# Radio2_Cm.net
KiCad netlist of a schematic drawn in EAGLE
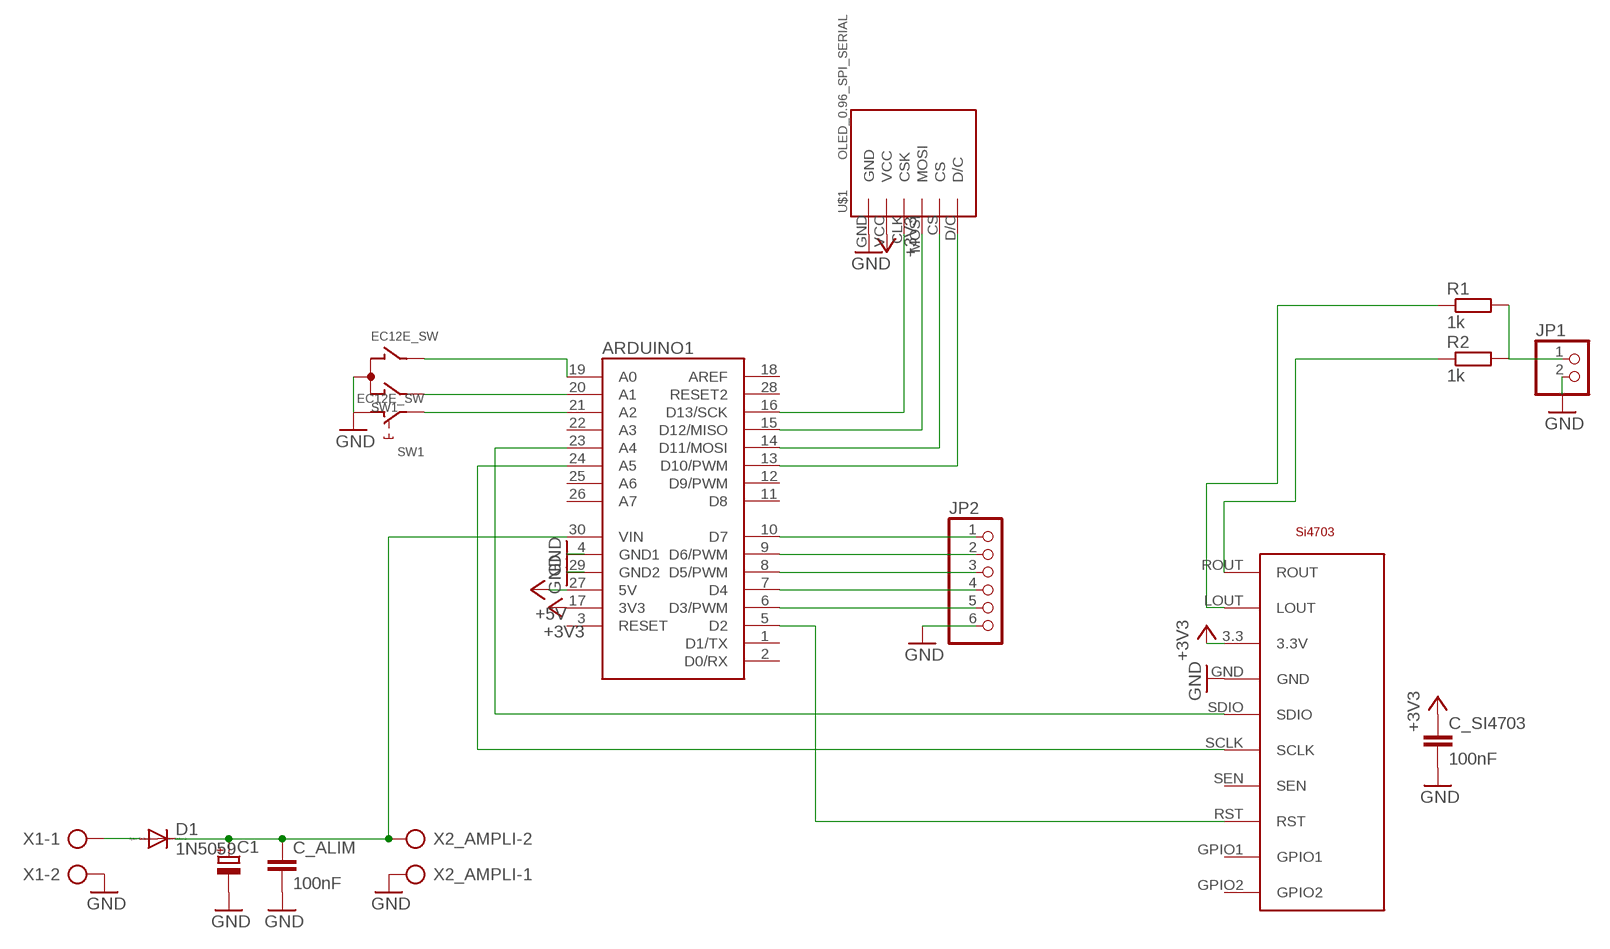
[diagram p0: schematic, sheet 1]

(export (version "E")
  (design (tool "Eeschema 10.0.6"))
  (components
    (comp (ref "ARDUINO1")
      (value "ARDUINO_NANO")
      (footprint "eagle-import:ARDUINO_NANO")
      (libsource (lib "eagle-import") (part "ARDUINO_NANO"))
    )
    (comp (ref "C1")
      (value "CPOL-EUE7.5-16")
      (footprint "eagle-import:E7,5-16")
      (libsource (lib "eagle-import") (part "CPOL-EUE7.5-16"))
    )
    (comp (ref "C_ALIM")
      (value "100nF")
      (footprint "eagle-import:C025-024X044")
      (libsource (lib "eagle-import") (part "C-EU025-024X044"))
    )
    (comp (ref "C_SI4703")
      (value "100nF")
      (footprint "eagle-import:C025-024X044")
      (libsource (lib "eagle-import") (part "C-EU025-024X044"))
    )
    (comp (ref "D1")
      (value "1N5059")
      (footprint "eagle-import:DO204-10")
      (libsource (lib "eagle-import") (part "1N5059"))
    )
    (comp (ref "JP1")
      (value "PINHD-1X2")
      (footprint "eagle-import:1X02")
      (libsource (lib "eagle-import") (part "PINHD-1X2"))
    )
    (comp (ref "JP2")
      (value "PINHD-1X6")
      (footprint "eagle-import:1X06")
      (libsource (lib "eagle-import") (part "PINHD-1X6"))
    )
    (comp (ref "R1")
      (value "1k")
      (footprint "eagle-import:0207_10")
      (libsource (lib "eagle-import") (part "R-EU_0207/10"))
    )
    (comp (ref "R2")
      (value "1k")
      (footprint "eagle-import:0207_10")
      (libsource (lib "eagle-import") (part "R-EU_0207/10"))
    )
    (comp (ref "SW1")
      (value "EC12E_SW")
      (footprint "eagle-import:ALPS_EC12E_SW")
      (fields (field (name "MPN") "EC12E2424407"))
      (libsource (lib "eagle-import") (part "EC12E_SW"))
    )
    (comp (ref "U$1")
      (value "OLED_0.96_SPI_SERIAL")
      (footprint "eagle-import:OLED_9.96_SPI_SERIAL")
      (libsource (lib "eagle-import") (part "OLED_0.96_SPI_SERIAL"))
    )
    (comp (ref "U$3")
      (value "SI4703")
      (footprint "eagle-import:SI4703")
      (libsource (lib "eagle-import") (part "SI4703"))
    )
    (comp (ref "X1")
      (value "AK300/2")
      (footprint "eagle-import:AK300_2")
      (libsource (lib "eagle-import") (part "AK300/2"))
    )
    (comp (ref "X2_AMPLI")
      (value "AK300/2")
      (footprint "eagle-import:AK300_2")
      (libsource (lib "eagle-import") (part "AK300/2"))
    )
  )
  (nets
    (net (code "1") (name "+3V3") (class "Default")
      (node (ref "ARDUINO1") (pin "17") (pinfunction "3V3_17") (pintype "power_in"))
      (node (ref "C_SI4703") (pin "1") (pinfunction "1_1") (pintype "passive"))
      (node (ref "U$1") (pin "VCC") (pinfunction "VCC_VCC") (pintype "bidirectional"))
      (node (ref "U$3") (pin "3.3") (pinfunction "3.3V_3.3") (pintype "bidirectional"))
    )
    (net (code "2") (name "+5V") (class "Default")
      (node (ref "ARDUINO1") (pin "27") (pinfunction "5V_27") (pintype "power_in"))
    )
    (net (code "3") (name "/RESET2") (class "Default")
      (node (ref "ARDUINO1") (pin "28") (pinfunction "RESET2_28") (pintype "power_in"))
    )
    (net (code "4") (name "GND") (class "Default")
      (node (ref "ARDUINO1") (pin "29") (pinfunction "GND2_29") (pintype "power_in"))
      (node (ref "ARDUINO1") (pin "4") (pinfunction "GND1_4") (pintype "power_in"))
      (node (ref "C1") (pin "-") (pinfunction "-_-") (pintype "passive"))
      (node (ref "C_ALIM") (pin "2") (pinfunction "2_2") (pintype "passive"))
      (node (ref "C_SI4703") (pin "2") (pinfunction "2_2") (pintype "passive"))
      (node (ref "JP1") (pin "2") (pinfunction "2_2") (pintype "passive"))
      (node (ref "JP2") (pin "6") (pinfunction "6_6") (pintype "passive"))
      (node (ref "SW1") (pin "C") (pinfunction "C_C") (pintype "passive"))
      (node (ref "SW1") (pin "D") (pinfunction "1_D") (pintype "passive"))
      (node (ref "U$1") (pin "GND") (pinfunction "GND_GND") (pintype "bidirectional"))
      (node (ref "U$3") (pin "GND") (pinfunction "GND_GND") (pintype "bidirectional"))
      (node (ref "X1") (pin "2") (pinfunction "KL_2") (pintype "passive"))
      (node (ref "X2_AMPLI") (pin "1") (pinfunction "KL_1") (pintype "passive"))
    )
    (net (code "5") (name "Net-(ARDUINO1-A0)") (class "Default")
      (node (ref "ARDUINO1") (pin "19") (pinfunction "A0_19") (pintype "bidirectional"))
      (node (ref "SW1") (pin "B") (pinfunction "B_B") (pintype "passive"))
    )
    (net (code "6") (name "Net-(ARDUINO1-A1)") (class "Default")
      (node (ref "ARDUINO1") (pin "20") (pinfunction "A1_20") (pintype "bidirectional"))
      (node (ref "SW1") (pin "A") (pinfunction "A_A") (pintype "passive"))
    )
    (net (code "7") (name "Net-(ARDUINO1-A2)") (class "Default")
      (node (ref "ARDUINO1") (pin "21") (pinfunction "A2_21") (pintype "bidirectional"))
      (node (ref "SW1") (pin "E") (pinfunction "2_E") (pintype "passive"))
    )
    (net (code "8") (name "Net-(ARDUINO1-A4)") (class "Default")
      (node (ref "ARDUINO1") (pin "23") (pinfunction "A4_23") (pintype "bidirectional"))
      (node (ref "U$3") (pin "SDIO") (pinfunction "SDIO_SDIO") (pintype "bidirectional"))
    )
    (net (code "9") (name "Net-(ARDUINO1-A5)") (class "Default")
      (node (ref "ARDUINO1") (pin "24") (pinfunction "A5_24") (pintype "bidirectional"))
      (node (ref "U$3") (pin "SCLK") (pinfunction "SCLK_SCLK") (pintype "bidirectional"))
    )
    (net (code "10") (name "Net-(ARDUINO1-D2)") (class "Default")
      (node (ref "ARDUINO1") (pin "5") (pinfunction "D2_5") (pintype "bidirectional"))
      (node (ref "U$3") (pin "RST") (pinfunction "RST_RST") (pintype "bidirectional"))
    )
    (net (code "11") (name "Net-(ARDUINO1-D3{slash}PWM)") (class "Default")
      (node (ref "ARDUINO1") (pin "6") (pinfunction "D3/PWM_6") (pintype "bidirectional"))
      (node (ref "JP2") (pin "5") (pinfunction "5_5") (pintype "passive"))
    )
    (net (code "12") (name "Net-(ARDUINO1-D4)") (class "Default")
      (node (ref "ARDUINO1") (pin "7") (pinfunction "D4_7") (pintype "bidirectional"))
      (node (ref "JP2") (pin "4") (pinfunction "4_4") (pintype "passive"))
    )
    (net (code "13") (name "Net-(ARDUINO1-D5{slash}PWM)") (class "Default")
      (node (ref "ARDUINO1") (pin "8") (pinfunction "D5/PWM_8") (pintype "bidirectional"))
      (node (ref "JP2") (pin "3") (pinfunction "3_3") (pintype "passive"))
    )
    (net (code "14") (name "Net-(ARDUINO1-D6{slash}PWM)") (class "Default")
      (node (ref "ARDUINO1") (pin "9") (pinfunction "D6/PWM_9") (pintype "bidirectional"))
      (node (ref "JP2") (pin "2") (pinfunction "2_2") (pintype "passive"))
    )
    (net (code "15") (name "Net-(ARDUINO1-D7)") (class "Default")
      (node (ref "ARDUINO1") (pin "10") (pinfunction "D7_10") (pintype "bidirectional"))
      (node (ref "JP2") (pin "1") (pinfunction "1_1") (pintype "passive"))
    )
    (net (code "16") (name "Net-(ARDUINO1-D10{slash}PWM)") (class "Default")
      (node (ref "ARDUINO1") (pin "13") (pinfunction "D10/PWM_13") (pintype "bidirectional"))
      (node (ref "U$1") (pin "D/C") (pinfunction "D/C_D/C") (pintype "bidirectional"))
    )
    (net (code "17") (name "Net-(ARDUINO1-D11{slash}MOSI)") (class "Default")
      (node (ref "ARDUINO1") (pin "14") (pinfunction "D11/MOSI_14") (pintype "bidirectional"))
      (node (ref "U$1") (pin "CS") (pinfunction "CS_CS") (pintype "bidirectional"))
    )
    (net (code "18") (name "Net-(ARDUINO1-D12{slash}MISO)") (class "Default")
      (node (ref "ARDUINO1") (pin "15") (pinfunction "D12/MISO_15") (pintype "bidirectional"))
      (node (ref "U$1") (pin "MOSI") (pinfunction "MOSI_MOSI") (pintype "bidirectional"))
    )
    (net (code "19") (name "Net-(ARDUINO1-D13{slash}SCK)") (class "Default")
      (node (ref "ARDUINO1") (pin "16") (pinfunction "D13/SCK_16") (pintype "bidirectional"))
      (node (ref "U$1") (pin "CLK") (pinfunction "CSK_CLK") (pintype "bidirectional"))
    )
    (net (code "20") (name "Net-(ARDUINO1-VIN)") (class "Default")
      (node (ref "ARDUINO1") (pin "30") (pinfunction "VIN_30") (pintype "bidirectional"))
      (node (ref "C1") (pin "+") (pinfunction "+_+") (pintype "passive"))
      (node (ref "C_ALIM") (pin "1") (pinfunction "1_1") (pintype "passive"))
      (node (ref "D1") (pin "C") (pinfunction "C_C") (pintype "passive"))
      (node (ref "X2_AMPLI") (pin "2") (pinfunction "KL_2") (pintype "passive"))
    )
    (net (code "21") (name "Net-(JP1-Pad1)") (class "Default")
      (node (ref "JP1") (pin "1") (pinfunction "1_1") (pintype "passive"))
      (node (ref "R1") (pin "2") (pinfunction "2_2") (pintype "passive"))
      (node (ref "R2") (pin "2") (pinfunction "2_2") (pintype "passive"))
    )
    (net (code "22") (name "Net-(R1-Pad1)") (class "Default")
      (node (ref "R1") (pin "1") (pinfunction "1_1") (pintype "passive"))
      (node (ref "U$3") (pin "LOUT") (pinfunction "LOUT_LOUT") (pintype "bidirectional"))
    )
    (net (code "23") (name "Net-(R2-Pad1)") (class "Default")
      (node (ref "R2") (pin "1") (pinfunction "1_1") (pintype "passive"))
      (node (ref "U$3") (pin "ROUT") (pinfunction "ROUT_ROUT") (pintype "bidirectional"))
    )
    (net (code "24") (name "Net-(X1A-KL)") (class "Default")
      (node (ref "D1") (pin "A") (pinfunction "A_A") (pintype "passive"))
      (node (ref "X1") (pin "1") (pinfunction "KL_1") (pintype "passive"))
    )
    (net (code "25") (name "unconnected-(ARDUINO1-A3-Pad22)") (class "Default")
      (node (ref "ARDUINO1") (pin "22") (pinfunction "A3_22") (pintype "bidirectional"))
    )
    (net (code "26") (name "unconnected-(ARDUINO1-A6-Pad25)") (class "Default")
      (node (ref "ARDUINO1") (pin "25") (pinfunction "A6_25") (pintype "bidirectional"))
    )
    (net (code "27") (name "unconnected-(ARDUINO1-A7-Pad26)") (class "Default")
      (node (ref "ARDUINO1") (pin "26") (pinfunction "A7_26") (pintype "bidirectional"))
    )
    (net (code "28") (name "unconnected-(ARDUINO1-AREF-Pad18)") (class "Default")
      (node (ref "ARDUINO1") (pin "18") (pinfunction "AREF_18") (pintype "bidirectional"))
    )
    (net (code "29") (name "unconnected-(ARDUINO1-D0{slash}RX-Pad2)") (class "Default")
      (node (ref "ARDUINO1") (pin "2") (pinfunction "D0/RX_2") (pintype "bidirectional"))
    )
    (net (code "30") (name "unconnected-(ARDUINO1-D1{slash}TX-Pad1)") (class "Default")
      (node (ref "ARDUINO1") (pin "1") (pinfunction "D1/TX_1") (pintype "bidirectional"))
    )
    (net (code "31") (name "unconnected-(ARDUINO1-D8-Pad11)") (class "Default")
      (node (ref "ARDUINO1") (pin "11") (pinfunction "D8_11") (pintype "bidirectional"))
    )
    (net (code "32") (name "unconnected-(ARDUINO1-D9{slash}PWM-Pad12)") (class "Default")
      (node (ref "ARDUINO1") (pin "12") (pinfunction "D9/PWM_12") (pintype "bidirectional"))
    )
    (net (code "33") (name "unconnected-(ARDUINO1-RESET-Pad3)") (class "Default")
      (node (ref "ARDUINO1") (pin "3") (pinfunction "RESET_3") (pintype "bidirectional"))
    )
    (net (code "34") (name "unconnected-(U$3-PadGPIO1)") (class "Default")
      (node (ref "U$3") (pin "GPIO1") (pinfunction "GPIO1_GPIO1") (pintype "bidirectional"))
    )
    (net (code "35") (name "unconnected-(U$3-PadGPIO2)") (class "Default")
      (node (ref "U$3") (pin "GPIO2") (pinfunction "GPIO2_GPIO2") (pintype "bidirectional"))
    )
    (net (code "36") (name "unconnected-(U$3-PadSEN)") (class "Default")
      (node (ref "U$3") (pin "SEN") (pinfunction "SEN_SEN") (pintype "bidirectional"))
    )
  )
)
